# ethernet_board.net
KiCad netlist of a schematic drawn in EAGLE
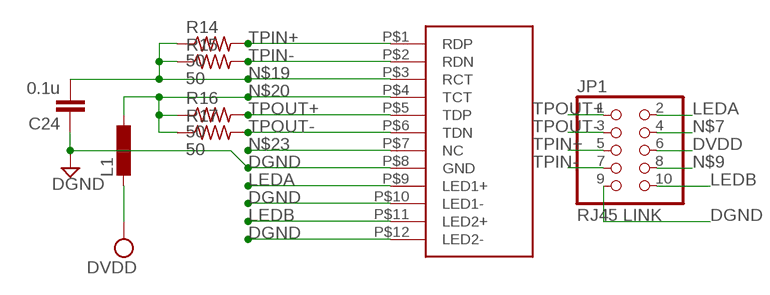
[diagram p0: schematic, sheet 1]

(export (version "E")
  (design (tool "Eeschema 10.0.6"))
  (components
    (comp (ref "C24")
      (value "0.1u")
      (footprint "eagle-import:C0805")
      (libsource (lib "eagle-import") (part "C-EUC0805"))
    )
    (comp (ref "JP1")
      (value "RJ45 LINK")
      (footprint "eagle-import:2X05_90")
      (libsource (lib "eagle-import") (part "PINHD-2X5/90"))
    )
    (comp (ref "L1")
      (value "L-EU0207/10")
      (footprint "eagle-import:0207_10")
      (libsource (lib "eagle-import") (part "L-EU0207/10"))
    )
    (comp (ref "R14")
      (value "50")
      (footprint "eagle-import:R1206")
      (libsource (lib "eagle-import") (part "R-US_R1206"))
    )
    (comp (ref "R15")
      (value "50")
      (footprint "eagle-import:R1206")
      (libsource (lib "eagle-import") (part "R-US_R1206"))
    )
    (comp (ref "R16")
      (value "50")
      (footprint "eagle-import:R1206")
      (libsource (lib "eagle-import") (part "R-US_R1206"))
    )
    (comp (ref "R17")
      (value "50")
      (footprint "eagle-import:R1206")
      (libsource (lib "eagle-import") (part "R-US_R1206"))
    )
    (comp (ref "U$5")
      (value "RJ45")
      (footprint "eagle-import:TYCO-RJ45")
      (libsource (lib "eagle-import") (part "TYCO-RJ45"))
    )
  )
  (nets
    (net (code "1") (name "/LEDA") (class "Default")
      (node (ref "JP1") (pin "2") (pinfunction "2_2") (pintype "passive"))
      (node (ref "U$5") (pin "P$9") (pinfunction "LED1+_P$9") (pintype "bidirectional"))
    )
    (net (code "2") (name "/LEDB") (class "Default")
      (node (ref "JP1") (pin "10") (pinfunction "10_10") (pintype "passive"))
      (node (ref "U$5") (pin "P$11") (pinfunction "LED2+_P$11") (pintype "bidirectional"))
    )
    (net (code "3") (name "/N$7") (class "Default")
      (node (ref "JP1") (pin "4") (pinfunction "4_4") (pintype "passive"))
    )
    (net (code "4") (name "/N$9") (class "Default")
      (node (ref "JP1") (pin "8") (pinfunction "8_8") (pintype "passive"))
    )
    (net (code "5") (name "/N$19") (class "Default")
      (node (ref "C24") (pin "2") (pinfunction "2_2") (pintype "passive"))
      (node (ref "R14") (pin "1") (pinfunction "1_1") (pintype "passive"))
      (node (ref "R15") (pin "1") (pinfunction "1_1") (pintype "passive"))
      (node (ref "U$5") (pin "P$3") (pinfunction "RCT_P$3") (pintype "bidirectional"))
    )
    (net (code "6") (name "/N$20") (class "Default")
      (node (ref "L1") (pin "1") (pinfunction "1_1") (pintype "passive"))
      (node (ref "R16") (pin "1") (pinfunction "1_1") (pintype "passive"))
      (node (ref "R17") (pin "1") (pinfunction "1_1") (pintype "passive"))
      (node (ref "U$5") (pin "P$4") (pinfunction "TCT_P$4") (pintype "bidirectional"))
    )
    (net (code "7") (name "/N$23") (class "Default")
      (node (ref "U$5") (pin "P$7") (pinfunction "NC_P$7") (pintype "bidirectional"))
    )
    (net (code "8") (name "/TPIN+") (class "Default")
      (node (ref "JP1") (pin "5") (pinfunction "5_5") (pintype "passive"))
      (node (ref "R14") (pin "2") (pinfunction "2_2") (pintype "passive"))
      (node (ref "U$5") (pin "P$1") (pinfunction "RDP_P$1") (pintype "bidirectional"))
    )
    (net (code "9") (name "/TPIN-") (class "Default")
      (node (ref "JP1") (pin "7") (pinfunction "7_7") (pintype "passive"))
      (node (ref "R15") (pin "2") (pinfunction "2_2") (pintype "passive"))
      (node (ref "U$5") (pin "P$2") (pinfunction "RDN_P$2") (pintype "bidirectional"))
    )
    (net (code "10") (name "/TPOUT+") (class "Default")
      (node (ref "JP1") (pin "1") (pinfunction "1_1") (pintype "passive"))
      (node (ref "R16") (pin "2") (pinfunction "2_2") (pintype "passive"))
      (node (ref "U$5") (pin "P$5") (pinfunction "TDP_P$5") (pintype "bidirectional"))
    )
    (net (code "11") (name "/TPOUT-") (class "Default")
      (node (ref "JP1") (pin "3") (pinfunction "3_3") (pintype "passive"))
      (node (ref "R17") (pin "2") (pinfunction "2_2") (pintype "passive"))
      (node (ref "U$5") (pin "P$6") (pinfunction "TDN_P$6") (pintype "bidirectional"))
    )
    (net (code "12") (name "DGND") (class "Default")
      (node (ref "C24") (pin "1") (pinfunction "1_1") (pintype "passive"))
      (node (ref "JP1") (pin "9") (pinfunction "9_9") (pintype "passive"))
      (node (ref "U$5") (pin "P$10") (pinfunction "LED1-_P$10") (pintype "bidirectional"))
      (node (ref "U$5") (pin "P$12") (pinfunction "LED2-_P$12") (pintype "bidirectional"))
      (node (ref "U$5") (pin "P$8") (pinfunction "GND_P$8") (pintype "bidirectional"))
    )
    (net (code "13") (name "DVDD") (class "Default")
      (node (ref "JP1") (pin "6") (pinfunction "6_6") (pintype "passive"))
      (node (ref "L1") (pin "2") (pinfunction "2_2") (pintype "passive"))
    )
  )
)
